# inverted_board1.net
KiCad netlist of a schematic drawn in EasyEDA Pro
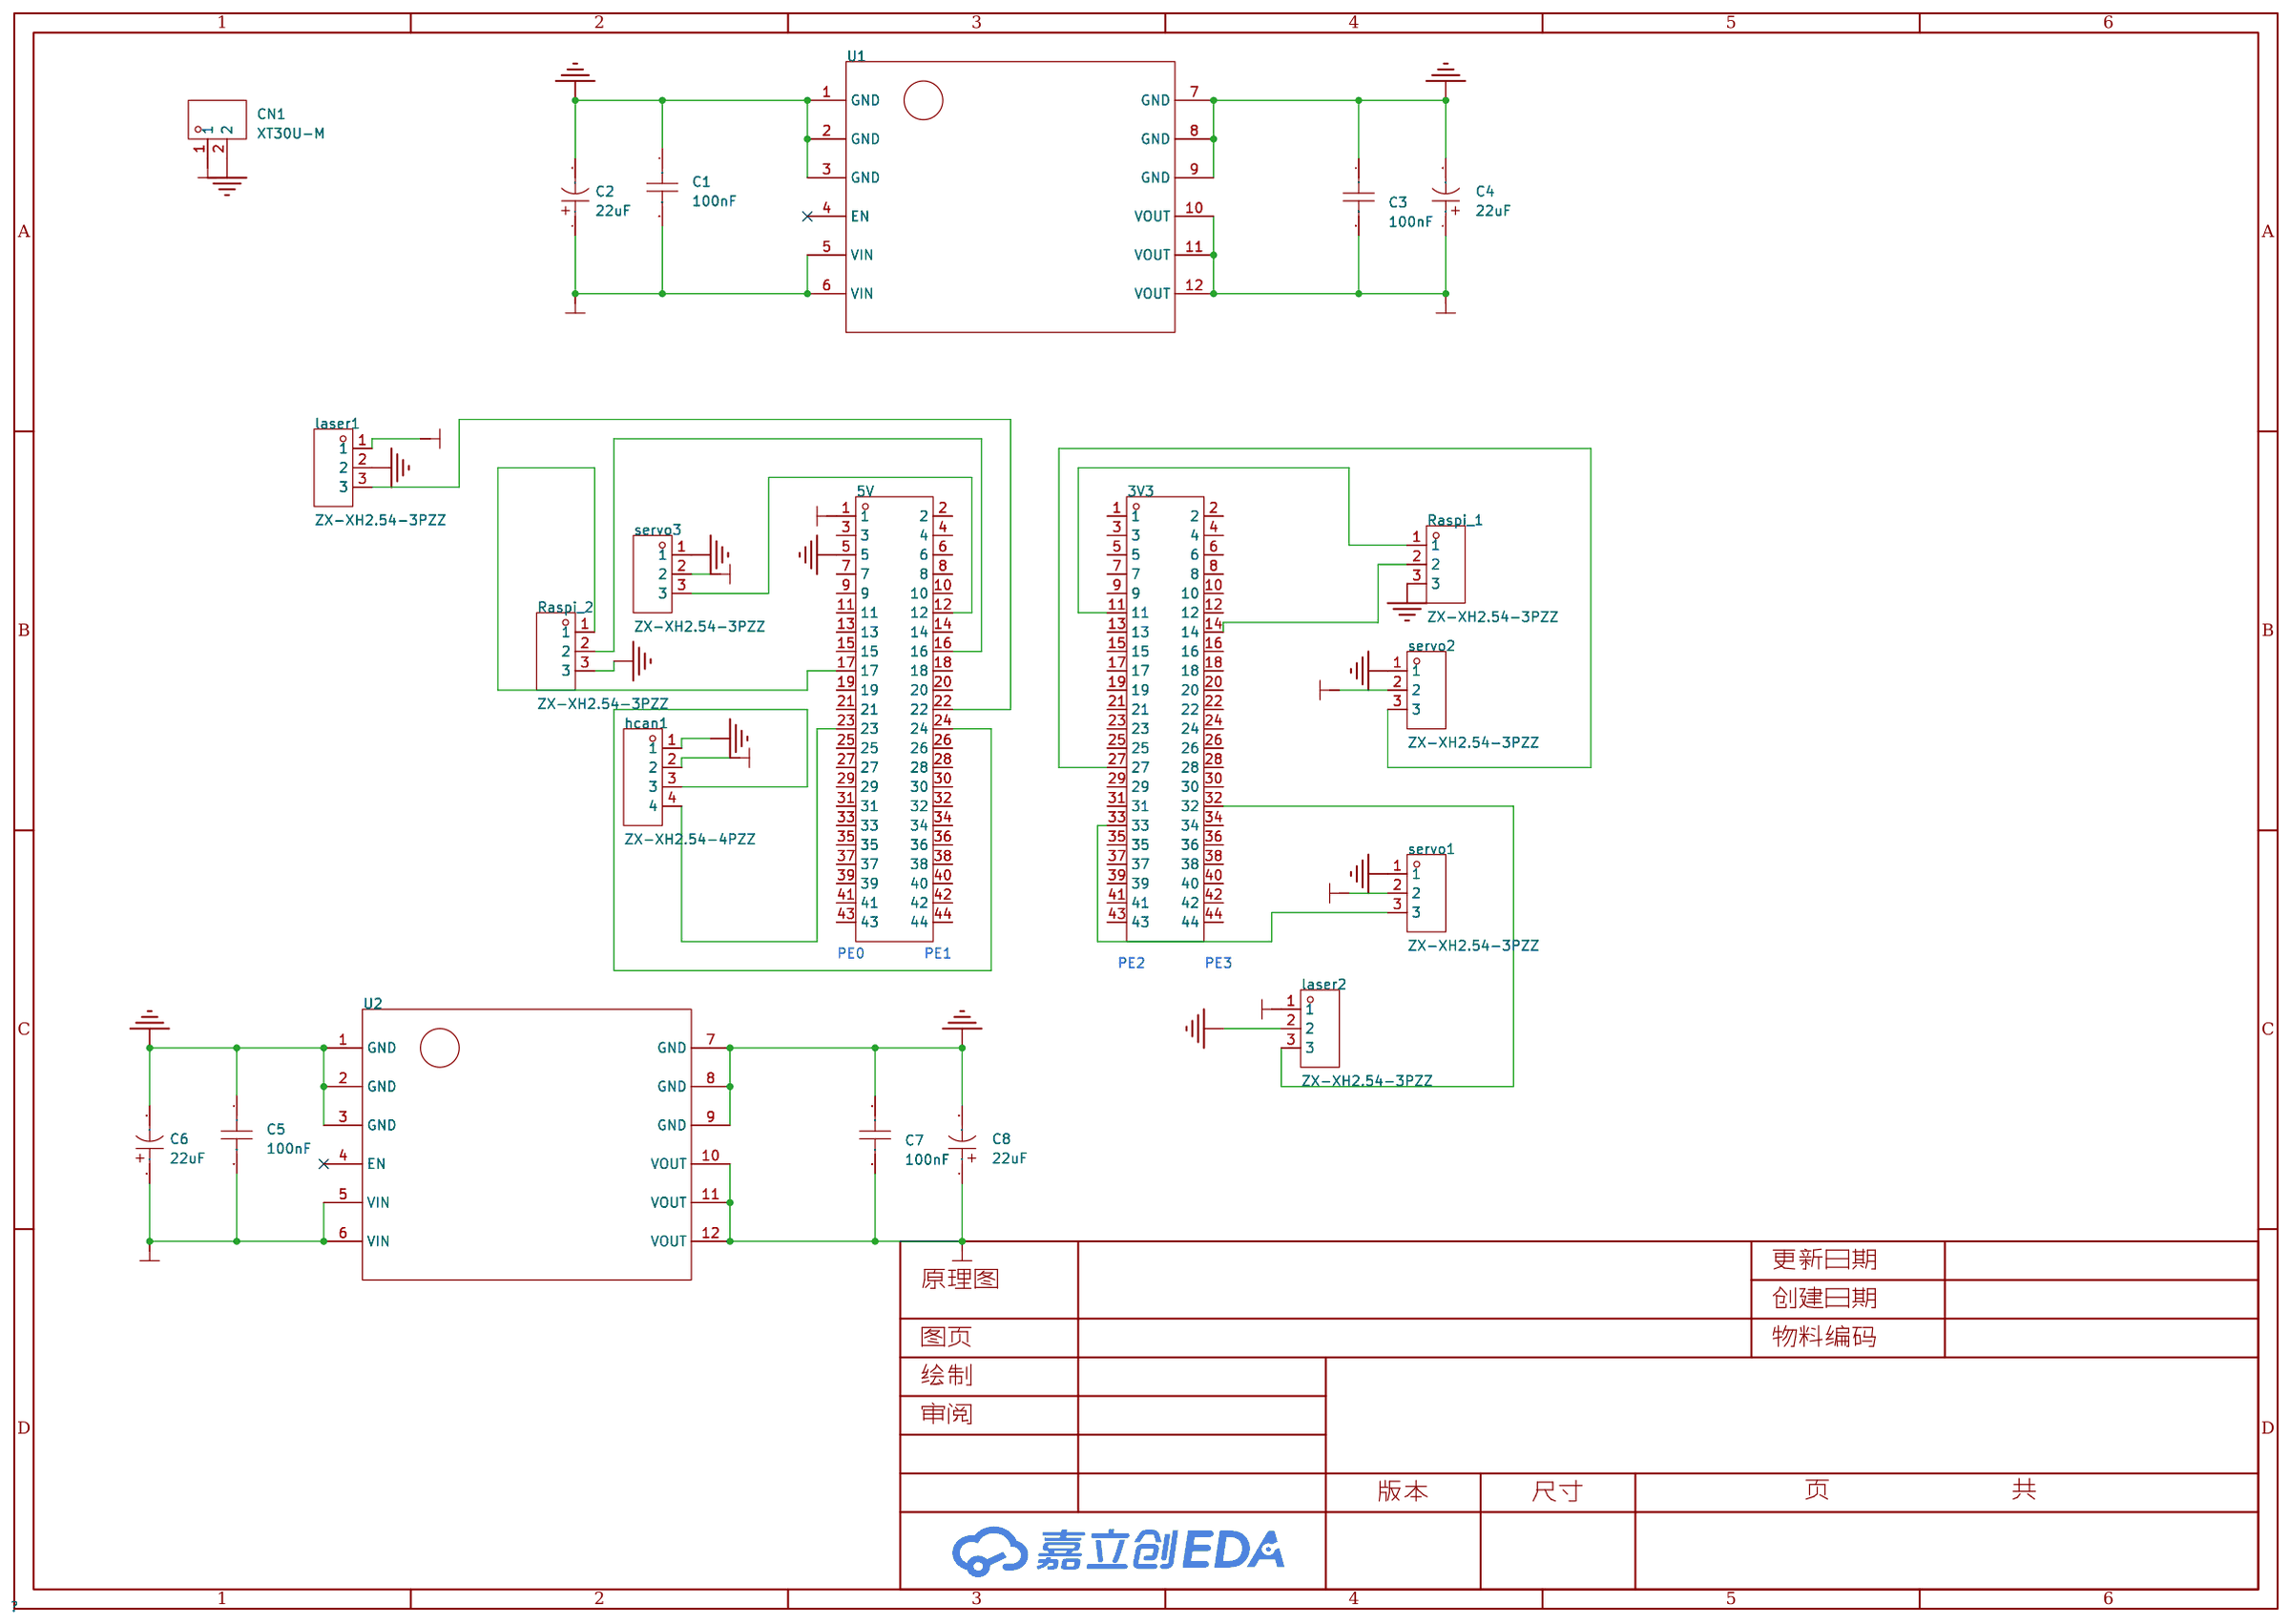
[diagram p0: schematic sheet]

(export (version "E")
  (design (tool "Eeschema 10.0.6"))
  (components
    (comp (ref "3V3")
      (value "X6521FV-2x22-C85D32")
      (footprint "easyedapro:HDR-TH_44P-P2.54-V-F-R2-C22-S2.54")
      (fields (field (name "Manufacturer") "XKB Connection(中国星坤)"))
      (libsource (lib "easyedapro") (part "X6521FV-2X22-C85D32"))
    )
    (comp (ref "5V")
      (value "X6521FV-2x22-C85D32")
      (footprint "easyedapro:HDR-TH_44P-P2.54-V-F-R2-C22-S2.54")
      (fields (field (name "Manufacturer") "XKB Connection(中国星坤)"))
      (libsource (lib "easyedapro") (part "X6521FV-2X22-C85D32"))
    )
    (comp (ref "C1")
      (value "100nF")
      (footprint "easyedapro:C0603")
      (description "容值:100nF;精度:±10%;额定电压:50V;温度系数:X7R;")
      (fields
        (field (name "Manufacturer Part") "CGA0603X7R104K500JT")
        (field (name "Manufacturer") "HRE(芯声)")
      )
      (libsource (lib "easyedapro") (part "CGA0603X7R104K500JT"))
    )
    (comp (ref "C2")
      (value "22uF")
      (footprint "easyedapro:CAP-TH_BD8.0-P5.00-D0.6-FD")
      (description "容值:22uF;额定电压:400V;")
      (fields
        (field (name "Manufacturer Part") "CD110226M2G0816VFL")
        (field (name "Manufacturer") "HRK(鸿瑞凯)")
      )
      (libsource (lib "easyedapro") (part "CD110226M2G0816VFL"))
    )
    (comp (ref "C3")
      (value "100nF")
      (footprint "easyedapro:C0603")
      (description "容值:100nF;精度:±10%;额定电压:50V;温度系数:X7R;")
      (fields
        (field (name "Manufacturer Part") "CGA0603X7R104K500JT")
        (field (name "Manufacturer") "HRE(芯声)")
      )
      (libsource (lib "easyedapro") (part "CGA0603X7R104K500JT"))
    )
    (comp (ref "C4")
      (value "22uF")
      (footprint "easyedapro:CAP-TH_BD8.0-P5.00-D0.6-FD")
      (description "容值:22uF;额定电压:400V;")
      (fields
        (field (name "Manufacturer Part") "CD110226M2G0816VFL")
        (field (name "Manufacturer") "HRK(鸿瑞凯)")
      )
      (libsource (lib "easyedapro") (part "CD110226M2G0816VFL"))
    )
    (comp (ref "C5")
      (value "100nF")
      (footprint "easyedapro:C0603")
      (description "容值:100nF;精度:±10%;额定电压:50V;温度系数:X7R;")
      (fields
        (field (name "Manufacturer Part") "CGA0603X7R104K500JT")
        (field (name "Manufacturer") "HRE(芯声)")
      )
      (libsource (lib "easyedapro") (part "CGA0603X7R104K500JT"))
    )
    (comp (ref "C6")
      (value "22uF")
      (footprint "easyedapro:CAP-TH_BD8.0-P5.00-D0.6-FD")
      (description "容值:22uF;额定电压:400V;")
      (fields
        (field (name "Manufacturer Part") "CD110226M2G0816VFL")
        (field (name "Manufacturer") "HRK(鸿瑞凯)")
      )
      (libsource (lib "easyedapro") (part "CD110226M2G0816VFL"))
    )
    (comp (ref "C7")
      (value "100nF")
      (footprint "easyedapro:C0603")
      (description "容值:100nF;精度:±10%;额定电压:50V;温度系数:X7R;")
      (fields
        (field (name "Manufacturer Part") "CGA0603X7R104K500JT")
        (field (name "Manufacturer") "HRE(芯声)")
      )
      (libsource (lib "easyedapro") (part "CGA0603X7R104K500JT"))
    )
    (comp (ref "C8")
      (value "22uF")
      (footprint "easyedapro:CAP-TH_BD8.0-P5.00-D0.6-FD")
      (description "容值:22uF;额定电压:400V;")
      (fields
        (field (name "Manufacturer Part") "CD110226M2G0816VFL")
        (field (name "Manufacturer") "HRK(鸿瑞凯)")
      )
      (libsource (lib "easyedapro") (part "CD110226M2G0816VFL"))
    )
    (comp (ref "CN1")
      (value "XT30U-M")
      (footprint "easyedapro:CONN-TH_XT30U-M")
      (description "类别:-;类型1:-;")
      (fields (field (name "Manufacturer") "AMASS(艾迈斯)"))
      (libsource (lib "easyedapro") (part "XT30U-M"))
    )
    (comp (ref "hcan1")
      (value "ZX-XH2.54-4PZZ")
      (footprint "easyedapro:CONN-TH_4P-P2.50_4PIN")
      (fields (field (name "Manufacturer") "Megastar(兆星)"))
      (libsource (lib "easyedapro") (part "ZX-XH2.54-4PZZ"))
    )
    (comp (ref "laser1")
      (value "ZX-XH2.54-3PZZ")
      (footprint "easyedapro:CONN-TH_3P-P2.54_2501S-3P")
      (fields (field (name "Manufacturer") "Megastar(兆星)"))
      (libsource (lib "easyedapro") (part "ZX-XH2.54-3PZZ"))
    )
    (comp (ref "laser2")
      (value "ZX-XH2.54-3PZZ")
      (footprint "easyedapro:CONN-TH_3P-P2.54_2501S-3P")
      (fields (field (name "Manufacturer") "Megastar(兆星)"))
      (libsource (lib "easyedapro") (part "ZX-XH2.54-3PZZ"))
    )
    (comp (ref "Raspi_1")
      (value "ZX-XH2.54-3PZZ")
      (footprint "easyedapro:CONN-TH_3P-P2.54_2501S-3P")
      (fields (field (name "Manufacturer") "Megastar(兆星)"))
      (libsource (lib "easyedapro") (part "ZX-XH2.54-3PZZ"))
    )
    (comp (ref "Raspi_2")
      (value "ZX-XH2.54-3PZZ")
      (footprint "easyedapro:CONN-TH_3P-P2.54_2501S-3P")
      (fields (field (name "Manufacturer") "Megastar(兆星)"))
      (libsource (lib "easyedapro") (part "ZX-XH2.54-3PZZ"))
    )
    (comp (ref "servo1")
      (value "ZX-XH2.54-3PZZ")
      (footprint "easyedapro:CONN-TH_3P-P2.54_2501S-3P")
      (fields (field (name "Manufacturer") "Megastar(兆星)"))
      (libsource (lib "easyedapro") (part "ZX-XH2.54-3PZZ"))
    )
    (comp (ref "servo2")
      (value "ZX-XH2.54-3PZZ")
      (footprint "easyedapro:CONN-TH_3P-P2.54_2501S-3P")
      (fields (field (name "Manufacturer") "Megastar(兆星)"))
      (libsource (lib "easyedapro") (part "ZX-XH2.54-3PZZ"))
    )
    (comp (ref "servo3")
      (value "ZX-XH2.54-3PZZ")
      (footprint "easyedapro:CONN-TH_3P-P2.54_2501S-3P")
      (fields (field (name "Manufacturer") "Megastar(兆星)"))
      (libsource (lib "easyedapro") (part "ZX-XH2.54-3PZZ"))
    )
    (comp (ref "U1")
      (value "~")
      (footprint "easyedapro:TPS5430")
      (libsource (lib "easyedapro") (part "12V-5V"))
    )
    (comp (ref "U2")
      (value "~")
      (footprint "easyedapro:TPS5430")
      (libsource (lib "easyedapro") (part "12V-5V"))
    )
  )
  (nets
    (net (code "1") (name "GND") (class "Default")
      (node (ref "5V") (pin "5") (pinfunction "5_5") (pintype "unspecified"))
      (node (ref "C1") (pin "1") (pinfunction "1_1") (pintype "unspecified"))
      (node (ref "C2") (pin "2") (pinfunction "2_2") (pintype "input"))
      (node (ref "C3") (pin "1") (pinfunction "1_1") (pintype "unspecified"))
      (node (ref "C4") (pin "2") (pinfunction "2_2") (pintype "input"))
      (node (ref "C5") (pin "1") (pinfunction "1_1") (pintype "unspecified"))
      (node (ref "C6") (pin "2") (pinfunction "2_2") (pintype "input"))
      (node (ref "C7") (pin "1") (pinfunction "1_1") (pintype "unspecified"))
      (node (ref "C8") (pin "2") (pinfunction "2_2") (pintype "input"))
      (node (ref "CN1") (pin "2") (pinfunction "2_2") (pintype "unspecified"))
      (node (ref "Raspi_1") (pin "3") (pinfunction "3_3") (pintype "unspecified"))
      (node (ref "Raspi_2") (pin "3") (pinfunction "3_3") (pintype "unspecified"))
      (node (ref "U1") (pin "1") (pinfunction "GND_1") (pintype "input"))
      (node (ref "U1") (pin "2") (pinfunction "GND_2") (pintype "input"))
      (node (ref "U1") (pin "3") (pinfunction "GND_3") (pintype "input"))
      (node (ref "U1") (pin "7") (pinfunction "GND_7") (pintype "input"))
      (node (ref "U1") (pin "8") (pinfunction "GND_8") (pintype "input"))
      (node (ref "U1") (pin "9") (pinfunction "GND_9") (pintype "input"))
      (node (ref "U2") (pin "1") (pinfunction "GND_1") (pintype "input"))
      (node (ref "U2") (pin "2") (pinfunction "GND_2") (pintype "input"))
      (node (ref "U2") (pin "3") (pinfunction "GND_3") (pintype "input"))
      (node (ref "U2") (pin "7") (pinfunction "GND_7") (pintype "input"))
      (node (ref "U2") (pin "8") (pinfunction "GND_8") (pintype "input"))
      (node (ref "U2") (pin "9") (pinfunction "GND_9") (pintype "input"))
      (node (ref "hcan1") (pin "1") (pinfunction "1_1") (pintype "unspecified"))
      (node (ref "laser1") (pin "2") (pinfunction "2_2") (pintype "unspecified"))
      (node (ref "laser2") (pin "2") (pinfunction "2_2") (pintype "unspecified"))
      (node (ref "servo1") (pin "1") (pinfunction "1_1") (pintype "unspecified"))
      (node (ref "servo2") (pin "1") (pinfunction "1_1") (pintype "unspecified"))
      (node (ref "servo3") (pin "1") (pinfunction "1_1") (pintype "unspecified"))
    )
    (net (code "2") (name "Net-(3V3-Pad11)") (class "Default")
      (node (ref "3V3") (pin "11") (pinfunction "11_11") (pintype "unspecified"))
      (node (ref "Raspi_1") (pin "1") (pinfunction "1_1") (pintype "unspecified"))
    )
    (net (code "3") (name "Net-(3V3-Pad14)") (class "Default")
      (node (ref "3V3") (pin "14") (pinfunction "14_14") (pintype "unspecified"))
      (node (ref "Raspi_1") (pin "2") (pinfunction "2_2") (pintype "unspecified"))
    )
    (net (code "4") (name "Net-(3V3-Pad27)") (class "Default")
      (node (ref "3V3") (pin "27") (pinfunction "27_27") (pintype "unspecified"))
      (node (ref "servo2") (pin "3") (pinfunction "3_3") (pintype "unspecified"))
    )
    (net (code "5") (name "Net-(3V3-Pad32)") (class "Default")
      (node (ref "3V3") (pin "32") (pinfunction "32_32") (pintype "unspecified"))
      (node (ref "laser2") (pin "3") (pinfunction "3_3") (pintype "unspecified"))
    )
    (net (code "6") (name "Net-(3V3-Pad33)") (class "Default")
      (node (ref "3V3") (pin "33") (pinfunction "33_33") (pintype "unspecified"))
      (node (ref "servo1") (pin "3") (pinfunction "3_3") (pintype "unspecified"))
    )
    (net (code "7") (name "Net-(5V-Pad12)") (class "Default")
      (node (ref "5V") (pin "12") (pinfunction "12_12") (pintype "unspecified"))
      (node (ref "servo3") (pin "3") (pinfunction "3_3") (pintype "unspecified"))
    )
    (net (code "8") (name "Net-(5V-Pad16)") (class "Default")
      (node (ref "5V") (pin "16") (pinfunction "16_16") (pintype "unspecified"))
      (node (ref "Raspi_2") (pin "2") (pinfunction "2_2") (pintype "unspecified"))
    )
    (net (code "9") (name "Net-(5V-Pad17)") (class "Default")
      (node (ref "5V") (pin "17") (pinfunction "17_17") (pintype "unspecified"))
      (node (ref "Raspi_2") (pin "1") (pinfunction "1_1") (pintype "unspecified"))
    )
    (net (code "10") (name "Net-(5V-Pad22)") (class "Default")
      (node (ref "5V") (pin "22") (pinfunction "22_22") (pintype "unspecified"))
      (node (ref "laser1") (pin "3") (pinfunction "3_3") (pintype "unspecified"))
    )
    (net (code "11") (name "Net-(5V-Pad23)") (class "Default")
      (node (ref "5V") (pin "23") (pinfunction "23_23") (pintype "unspecified"))
      (node (ref "hcan1") (pin "4") (pinfunction "4_4") (pintype "unspecified"))
    )
    (net (code "12") (name "Net-(5V-Pad24)") (class "Default")
      (node (ref "5V") (pin "24") (pinfunction "24_24") (pintype "unspecified"))
      (node (ref "hcan1") (pin "3") (pinfunction "3_3") (pintype "unspecified"))
    )
    (net (code "13") (name "VIN") (class "Default")
      (node (ref "C1") (pin "2") (pinfunction "2_2") (pintype "unspecified"))
      (node (ref "C2") (pin "1") (pinfunction "1_1") (pintype "input"))
      (node (ref "C5") (pin "2") (pinfunction "2_2") (pintype "unspecified"))
      (node (ref "C6") (pin "1") (pinfunction "1_1") (pintype "input"))
      (node (ref "CN1") (pin "1") (pinfunction "1_1") (pintype "unspecified"))
      (node (ref "U1") (pin "5") (pinfunction "VIN_5") (pintype "input"))
      (node (ref "U1") (pin "6") (pinfunction "VIN_6") (pintype "input"))
      (node (ref "U2") (pin "5") (pinfunction "VIN_5") (pintype "input"))
      (node (ref "U2") (pin "6") (pinfunction "VIN_6") (pintype "input"))
    )
    (net (code "14") (name "VOUT_H") (class "Default")
      (node (ref "C3") (pin "2") (pinfunction "2_2") (pintype "unspecified"))
      (node (ref "C4") (pin "1") (pinfunction "1_1") (pintype "input"))
      (node (ref "U1") (pin "10") (pinfunction "VOUT_10") (pintype "input"))
      (node (ref "U1") (pin "11") (pinfunction "VOUT_11") (pintype "input"))
      (node (ref "U1") (pin "12") (pinfunction "VOUT_12") (pintype "input"))
      (node (ref "servo1") (pin "2") (pinfunction "2_2") (pintype "unspecified"))
      (node (ref "servo2") (pin "2") (pinfunction "2_2") (pintype "unspecified"))
      (node (ref "servo3") (pin "2") (pinfunction "2_2") (pintype "unspecified"))
    )
    (net (code "15") (name "VOUT_L") (class "Default")
      (node (ref "5V") (pin "1") (pinfunction "1_1") (pintype "unspecified"))
      (node (ref "C7") (pin "2") (pinfunction "2_2") (pintype "unspecified"))
      (node (ref "C8") (pin "1") (pinfunction "1_1") (pintype "input"))
      (node (ref "U2") (pin "10") (pinfunction "VOUT_10") (pintype "input"))
      (node (ref "U2") (pin "11") (pinfunction "VOUT_11") (pintype "input"))
      (node (ref "U2") (pin "12") (pinfunction "VOUT_12") (pintype "input"))
      (node (ref "hcan1") (pin "2") (pinfunction "2_2") (pintype "unspecified"))
      (node (ref "laser1") (pin "1") (pinfunction "1_1") (pintype "unspecified"))
      (node (ref "laser2") (pin "1") (pinfunction "1_1") (pintype "unspecified"))
    )
    (net (code "16") (name "unconnected-(3V3-Pad1)") (class "Default")
      (node (ref "3V3") (pin "1") (pinfunction "1_1") (pintype "unspecified"))
    )
    (net (code "17") (name "unconnected-(3V3-Pad2)") (class "Default")
      (node (ref "3V3") (pin "2") (pinfunction "2_2") (pintype "unspecified"))
    )
    (net (code "18") (name "unconnected-(3V3-Pad3)") (class "Default")
      (node (ref "3V3") (pin "3") (pinfunction "3_3") (pintype "unspecified"))
    )
    (net (code "19") (name "unconnected-(3V3-Pad4)") (class "Default")
      (node (ref "3V3") (pin "4") (pinfunction "4_4") (pintype "unspecified"))
    )
    (net (code "20") (name "unconnected-(3V3-Pad5)") (class "Default")
      (node (ref "3V3") (pin "5") (pinfunction "5_5") (pintype "unspecified"))
    )
    (net (code "21") (name "unconnected-(3V3-Pad6)") (class "Default")
      (node (ref "3V3") (pin "6") (pinfunction "6_6") (pintype "unspecified"))
    )
    (net (code "22") (name "unconnected-(3V3-Pad7)") (class "Default")
      (node (ref "3V3") (pin "7") (pinfunction "7_7") (pintype "unspecified"))
    )
    (net (code "23") (name "unconnected-(3V3-Pad8)") (class "Default")
      (node (ref "3V3") (pin "8") (pinfunction "8_8") (pintype "unspecified"))
    )
    (net (code "24") (name "unconnected-(3V3-Pad9)") (class "Default")
      (node (ref "3V3") (pin "9") (pinfunction "9_9") (pintype "unspecified"))
    )
    (net (code "25") (name "unconnected-(3V3-Pad10)") (class "Default")
      (node (ref "3V3") (pin "10") (pinfunction "10_10") (pintype "unspecified"))
    )
    (net (code "26") (name "unconnected-(3V3-Pad12)") (class "Default")
      (node (ref "3V3") (pin "12") (pinfunction "12_12") (pintype "unspecified"))
    )
    (net (code "27") (name "unconnected-(3V3-Pad13)") (class "Default")
      (node (ref "3V3") (pin "13") (pinfunction "13_13") (pintype "unspecified"))
    )
    (net (code "28") (name "unconnected-(3V3-Pad15)") (class "Default")
      (node (ref "3V3") (pin "15") (pinfunction "15_15") (pintype "unspecified"))
    )
    (net (code "29") (name "unconnected-(3V3-Pad16)") (class "Default")
      (node (ref "3V3") (pin "16") (pinfunction "16_16") (pintype "unspecified"))
    )
    (net (code "30") (name "unconnected-(3V3-Pad17)") (class "Default")
      (node (ref "3V3") (pin "17") (pinfunction "17_17") (pintype "unspecified"))
    )
    (net (code "31") (name "unconnected-(3V3-Pad18)") (class "Default")
      (node (ref "3V3") (pin "18") (pinfunction "18_18") (pintype "unspecified"))
    )
    (net (code "32") (name "unconnected-(3V3-Pad19)") (class "Default")
      (node (ref "3V3") (pin "19") (pinfunction "19_19") (pintype "unspecified"))
    )
    (net (code "33") (name "unconnected-(3V3-Pad20)") (class "Default")
      (node (ref "3V3") (pin "20") (pinfunction "20_20") (pintype "unspecified"))
    )
    (net (code "34") (name "unconnected-(3V3-Pad21)") (class "Default")
      (node (ref "3V3") (pin "21") (pinfunction "21_21") (pintype "unspecified"))
    )
    (net (code "35") (name "unconnected-(3V3-Pad22)") (class "Default")
      (node (ref "3V3") (pin "22") (pinfunction "22_22") (pintype "unspecified"))
    )
    (net (code "36") (name "unconnected-(3V3-Pad23)") (class "Default")
      (node (ref "3V3") (pin "23") (pinfunction "23_23") (pintype "unspecified"))
    )
    (net (code "37") (name "unconnected-(3V3-Pad24)") (class "Default")
      (node (ref "3V3") (pin "24") (pinfunction "24_24") (pintype "unspecified"))
    )
    (net (code "38") (name "unconnected-(3V3-Pad25)") (class "Default")
      (node (ref "3V3") (pin "25") (pinfunction "25_25") (pintype "unspecified"))
    )
    (net (code "39") (name "unconnected-(3V3-Pad26)") (class "Default")
      (node (ref "3V3") (pin "26") (pinfunction "26_26") (pintype "unspecified"))
    )
    (net (code "40") (name "unconnected-(3V3-Pad28)") (class "Default")
      (node (ref "3V3") (pin "28") (pinfunction "28_28") (pintype "unspecified"))
    )
    (net (code "41") (name "unconnected-(3V3-Pad29)") (class "Default")
      (node (ref "3V3") (pin "29") (pinfunction "29_29") (pintype "unspecified"))
    )
    (net (code "42") (name "unconnected-(3V3-Pad30)") (class "Default")
      (node (ref "3V3") (pin "30") (pinfunction "30_30") (pintype "unspecified"))
    )
    (net (code "43") (name "unconnected-(3V3-Pad31)") (class "Default")
      (node (ref "3V3") (pin "31") (pinfunction "31_31") (pintype "unspecified"))
    )
    (net (code "44") (name "unconnected-(3V3-Pad34)") (class "Default")
      (node (ref "3V3") (pin "34") (pinfunction "34_34") (pintype "unspecified"))
    )
    (net (code "45") (name "unconnected-(3V3-Pad35)") (class "Default")
      (node (ref "3V3") (pin "35") (pinfunction "35_35") (pintype "unspecified"))
    )
    (net (code "46") (name "unconnected-(3V3-Pad36)") (class "Default")
      (node (ref "3V3") (pin "36") (pinfunction "36_36") (pintype "unspecified"))
    )
    (net (code "47") (name "unconnected-(3V3-Pad37)") (class "Default")
      (node (ref "3V3") (pin "37") (pinfunction "37_37") (pintype "unspecified"))
    )
    (net (code "48") (name "unconnected-(3V3-Pad38)") (class "Default")
      (node (ref "3V3") (pin "38") (pinfunction "38_38") (pintype "unspecified"))
    )
    (net (code "49") (name "unconnected-(3V3-Pad39)") (class "Default")
      (node (ref "3V3") (pin "39") (pinfunction "39_39") (pintype "unspecified"))
    )
    (net (code "50") (name "unconnected-(3V3-Pad40)") (class "Default")
      (node (ref "3V3") (pin "40") (pinfunction "40_40") (pintype "unspecified"))
    )
    (net (code "51") (name "unconnected-(3V3-Pad41)") (class "Default")
      (node (ref "3V3") (pin "41") (pinfunction "41_41") (pintype "unspecified"))
    )
    (net (code "52") (name "unconnected-(3V3-Pad42)") (class "Default")
      (node (ref "3V3") (pin "42") (pinfunction "42_42") (pintype "unspecified"))
    )
    (net (code "53") (name "unconnected-(3V3-Pad43)") (class "Default")
      (node (ref "3V3") (pin "43") (pinfunction "43_43") (pintype "unspecified"))
    )
    (net (code "54") (name "unconnected-(3V3-Pad44)") (class "Default")
      (node (ref "3V3") (pin "44") (pinfunction "44_44") (pintype "unspecified"))
    )
    (net (code "55") (name "unconnected-(5V-Pad2)") (class "Default")
      (node (ref "5V") (pin "2") (pinfunction "2_2") (pintype "unspecified"))
    )
    (net (code "56") (name "unconnected-(5V-Pad3)") (class "Default")
      (node (ref "5V") (pin "3") (pinfunction "3_3") (pintype "unspecified"))
    )
    (net (code "57") (name "unconnected-(5V-Pad4)") (class "Default")
      (node (ref "5V") (pin "4") (pinfunction "4_4") (pintype "unspecified"))
    )
    (net (code "58") (name "unconnected-(5V-Pad6)") (class "Default")
      (node (ref "5V") (pin "6") (pinfunction "6_6") (pintype "unspecified"))
    )
    (net (code "59") (name "unconnected-(5V-Pad7)") (class "Default")
      (node (ref "5V") (pin "7") (pinfunction "7_7") (pintype "unspecified"))
    )
    (net (code "60") (name "unconnected-(5V-Pad8)") (class "Default")
      (node (ref "5V") (pin "8") (pinfunction "8_8") (pintype "unspecified"))
    )
    (net (code "61") (name "unconnected-(5V-Pad9)") (class "Default")
      (node (ref "5V") (pin "9") (pinfunction "9_9") (pintype "unspecified"))
    )
    (net (code "62") (name "unconnected-(5V-Pad10)") (class "Default")
      (node (ref "5V") (pin "10") (pinfunction "10_10") (pintype "unspecified"))
    )
    (net (code "63") (name "unconnected-(5V-Pad11)") (class "Default")
      (node (ref "5V") (pin "11") (pinfunction "11_11") (pintype "unspecified"))
    )
    (net (code "64") (name "unconnected-(5V-Pad13)") (class "Default")
      (node (ref "5V") (pin "13") (pinfunction "13_13") (pintype "unspecified"))
    )
    (net (code "65") (name "unconnected-(5V-Pad14)") (class "Default")
      (node (ref "5V") (pin "14") (pinfunction "14_14") (pintype "unspecified"))
    )
    (net (code "66") (name "unconnected-(5V-Pad15)") (class "Default")
      (node (ref "5V") (pin "15") (pinfunction "15_15") (pintype "unspecified"))
    )
    (net (code "67") (name "unconnected-(5V-Pad18)") (class "Default")
      (node (ref "5V") (pin "18") (pinfunction "18_18") (pintype "unspecified"))
    )
    (net (code "68") (name "unconnected-(5V-Pad19)") (class "Default")
      (node (ref "5V") (pin "19") (pinfunction "19_19") (pintype "unspecified"))
    )
    (net (code "69") (name "unconnected-(5V-Pad20)") (class "Default")
      (node (ref "5V") (pin "20") (pinfunction "20_20") (pintype "unspecified"))
    )
    (net (code "70") (name "unconnected-(5V-Pad21)") (class "Default")
      (node (ref "5V") (pin "21") (pinfunction "21_21") (pintype "unspecified"))
    )
    (net (code "71") (name "unconnected-(5V-Pad25)") (class "Default")
      (node (ref "5V") (pin "25") (pinfunction "25_25") (pintype "unspecified"))
    )
    (net (code "72") (name "unconnected-(5V-Pad26)") (class "Default")
      (node (ref "5V") (pin "26") (pinfunction "26_26") (pintype "unspecified"))
    )
    (net (code "73") (name "unconnected-(5V-Pad27)") (class "Default")
      (node (ref "5V") (pin "27") (pinfunction "27_27") (pintype "unspecified"))
    )
    (net (code "74") (name "unconnected-(5V-Pad28)") (class "Default")
      (node (ref "5V") (pin "28") (pinfunction "28_28") (pintype "unspecified"))
    )
    (net (code "75") (name "unconnected-(5V-Pad29)") (class "Default")
      (node (ref "5V") (pin "29") (pinfunction "29_29") (pintype "unspecified"))
    )
    (net (code "76") (name "unconnected-(5V-Pad30)") (class "Default")
      (node (ref "5V") (pin "30") (pinfunction "30_30") (pintype "unspecified"))
    )
    (net (code "77") (name "unconnected-(5V-Pad31)") (class "Default")
      (node (ref "5V") (pin "31") (pinfunction "31_31") (pintype "unspecified"))
    )
    (net (code "78") (name "unconnected-(5V-Pad32)") (class "Default")
      (node (ref "5V") (pin "32") (pinfunction "32_32") (pintype "unspecified"))
    )
    (net (code "79") (name "unconnected-(5V-Pad33)") (class "Default")
      (node (ref "5V") (pin "33") (pinfunction "33_33") (pintype "unspecified"))
    )
    (net (code "80") (name "unconnected-(5V-Pad34)") (class "Default")
      (node (ref "5V") (pin "34") (pinfunction "34_34") (pintype "unspecified"))
    )
    (net (code "81") (name "unconnected-(5V-Pad35)") (class "Default")
      (node (ref "5V") (pin "35") (pinfunction "35_35") (pintype "unspecified"))
    )
    (net (code "82") (name "unconnected-(5V-Pad36)") (class "Default")
      (node (ref "5V") (pin "36") (pinfunction "36_36") (pintype "unspecified"))
    )
    (net (code "83") (name "unconnected-(5V-Pad37)") (class "Default")
      (node (ref "5V") (pin "37") (pinfunction "37_37") (pintype "unspecified"))
    )
    (net (code "84") (name "unconnected-(5V-Pad38)") (class "Default")
      (node (ref "5V") (pin "38") (pinfunction "38_38") (pintype "unspecified"))
    )
    (net (code "85") (name "unconnected-(5V-Pad39)") (class "Default")
      (node (ref "5V") (pin "39") (pinfunction "39_39") (pintype "unspecified"))
    )
    (net (code "86") (name "unconnected-(5V-Pad40)") (class "Default")
      (node (ref "5V") (pin "40") (pinfunction "40_40") (pintype "unspecified"))
    )
    (net (code "87") (name "unconnected-(5V-Pad41)") (class "Default")
      (node (ref "5V") (pin "41") (pinfunction "41_41") (pintype "unspecified"))
    )
    (net (code "88") (name "unconnected-(5V-Pad42)") (class "Default")
      (node (ref "5V") (pin "42") (pinfunction "42_42") (pintype "unspecified"))
    )
    (net (code "89") (name "unconnected-(5V-Pad43)") (class "Default")
      (node (ref "5V") (pin "43") (pinfunction "43_43") (pintype "unspecified"))
    )
    (net (code "90") (name "unconnected-(5V-Pad44)") (class "Default")
      (node (ref "5V") (pin "44") (pinfunction "44_44") (pintype "unspecified"))
    )
    (net (code "91") (name "unconnected-(U1-EN-Pad4)") (class "Default")
      (node (ref "U1") (pin "4") (pinfunction "EN_4") (pintype "input+no_connect"))
    )
    (net (code "92") (name "unconnected-(U2-EN-Pad4)") (class "Default")
      (node (ref "U2") (pin "4") (pinfunction "EN_4") (pintype "input+no_connect"))
    )
  )
)
